# E_stop.net
KiCad netlist of a schematic drawn in Altium Designer
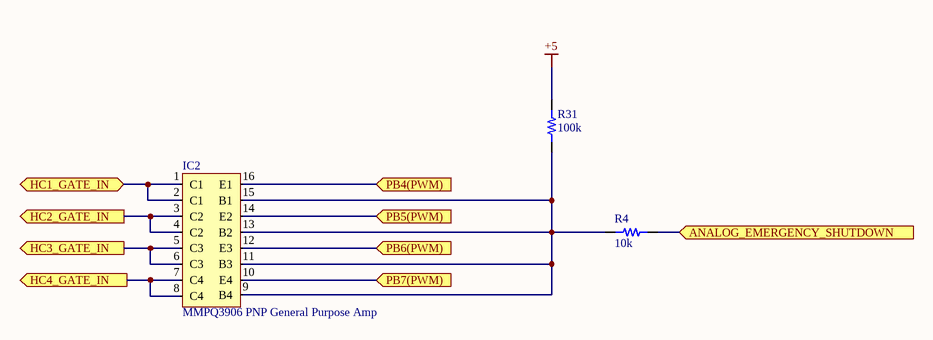
[diagram p0: E_stop.SchDoc]

(export (version "E")
  (design (tool "Eeschema 10.0.6"))
  (components
    (comp (ref "IC2")
      (value "MMPQ3906 PNP General Purpose Amp")
      (footprint "SOIC-16-NB")
      (libsource (lib "Altium-Lib") (part "MMPQ3906 PNP General Purpose Amp"))
    )
    (comp (ref "R4")
      (value "10k")
      (footprint "RES 0805/2012")
      (fields
        (field (name "TOLERANCE") "1%")
        (field (name "POWER") "1/10W")
        (field (name "Comment") "Resistor 10k 0805 1/10W 1%")
        (field (name "CREATED_BY") "Nick Mah")
      )
      (libsource (lib "Altium-Lib") (part "Resistor"))
    )
    (comp (ref "R31")
      (value "100k")
      (footprint "RES 0805/2012")
      (fields
        (field (name "TOLERANCE") "1%")
        (field (name "POWER") "1/2W")
        (field (name "Comment") "Resistor 100k 0805 1/2W 1%")
        (field (name "CREATED_BY") "Nick Mah")
      )
      (libsource (lib "Altium-Lib") (part "Resistor"))
    )
  )
  (nets
    (net (code "1") (name "+5") (class "Default")
      (node (ref "R31") (pin "2") (pinfunction "2_2") (pintype "passive"))
    )
    (net (code "2") (name "/ANALOG_EMERGENCY_SHUTDOWN") (class "Default")
      (node (ref "R4") (pin "2") (pinfunction "2_2") (pintype "passive"))
    )
    (net (code "3") (name "/HC1_GATE_IN") (class "Default")
      (node (ref "IC2") (pin "1") (pinfunction "C1_1") (pintype "input"))
      (node (ref "IC2") (pin "2") (pinfunction "C1_2") (pintype "input"))
    )
    (net (code "4") (name "/HC2_GATE_IN") (class "Default")
      (node (ref "IC2") (pin "3") (pinfunction "C2_3") (pintype "input"))
      (node (ref "IC2") (pin "4") (pinfunction "C2_4") (pintype "input"))
    )
    (net (code "5") (name "/HC3_GATE_IN") (class "Default")
      (node (ref "IC2") (pin "5") (pinfunction "C3_5") (pintype "input"))
      (node (ref "IC2") (pin "6") (pinfunction "C3_6") (pintype "input"))
    )
    (net (code "6") (name "/HC4_GATE_IN") (class "Default")
      (node (ref "IC2") (pin "7") (pinfunction "C4_7") (pintype "input"))
      (node (ref "IC2") (pin "8") (pinfunction "C4_8") (pintype "input"))
    )
    (net (code "7") (name "/PB4(PWM)") (class "Default")
      (node (ref "IC2") (pin "16") (pinfunction "E1_16") (pintype "input"))
    )
    (net (code "8") (name "/PB5(PWM)") (class "Default")
      (node (ref "IC2") (pin "14") (pinfunction "E2_14") (pintype "input"))
    )
    (net (code "9") (name "/PB6(PWM)") (class "Default")
      (node (ref "IC2") (pin "12") (pinfunction "E3_12") (pintype "input"))
    )
    (net (code "10") (name "/PB7(PWM)") (class "Default")
      (node (ref "IC2") (pin "10") (pinfunction "E4_10") (pintype "input"))
    )
    (net (code "11") (name "Net-(IC2-B1)") (class "Default")
      (node (ref "IC2") (pin "11") (pinfunction "B3_11") (pintype "input"))
      (node (ref "IC2") (pin "13") (pinfunction "B2_13") (pintype "input"))
      (node (ref "IC2") (pin "15") (pinfunction "B1_15") (pintype "input"))
      (node (ref "IC2") (pin "9") (pinfunction "B4_9") (pintype "input"))
      (node (ref "R31") (pin "1") (pinfunction "1_1") (pintype "passive"))
      (node (ref "R4") (pin "1") (pinfunction "1_1") (pintype "passive"))
    )
  )
)
